# IGNITERS.net
KiCad netlist of a schematic drawn in Altium Designer
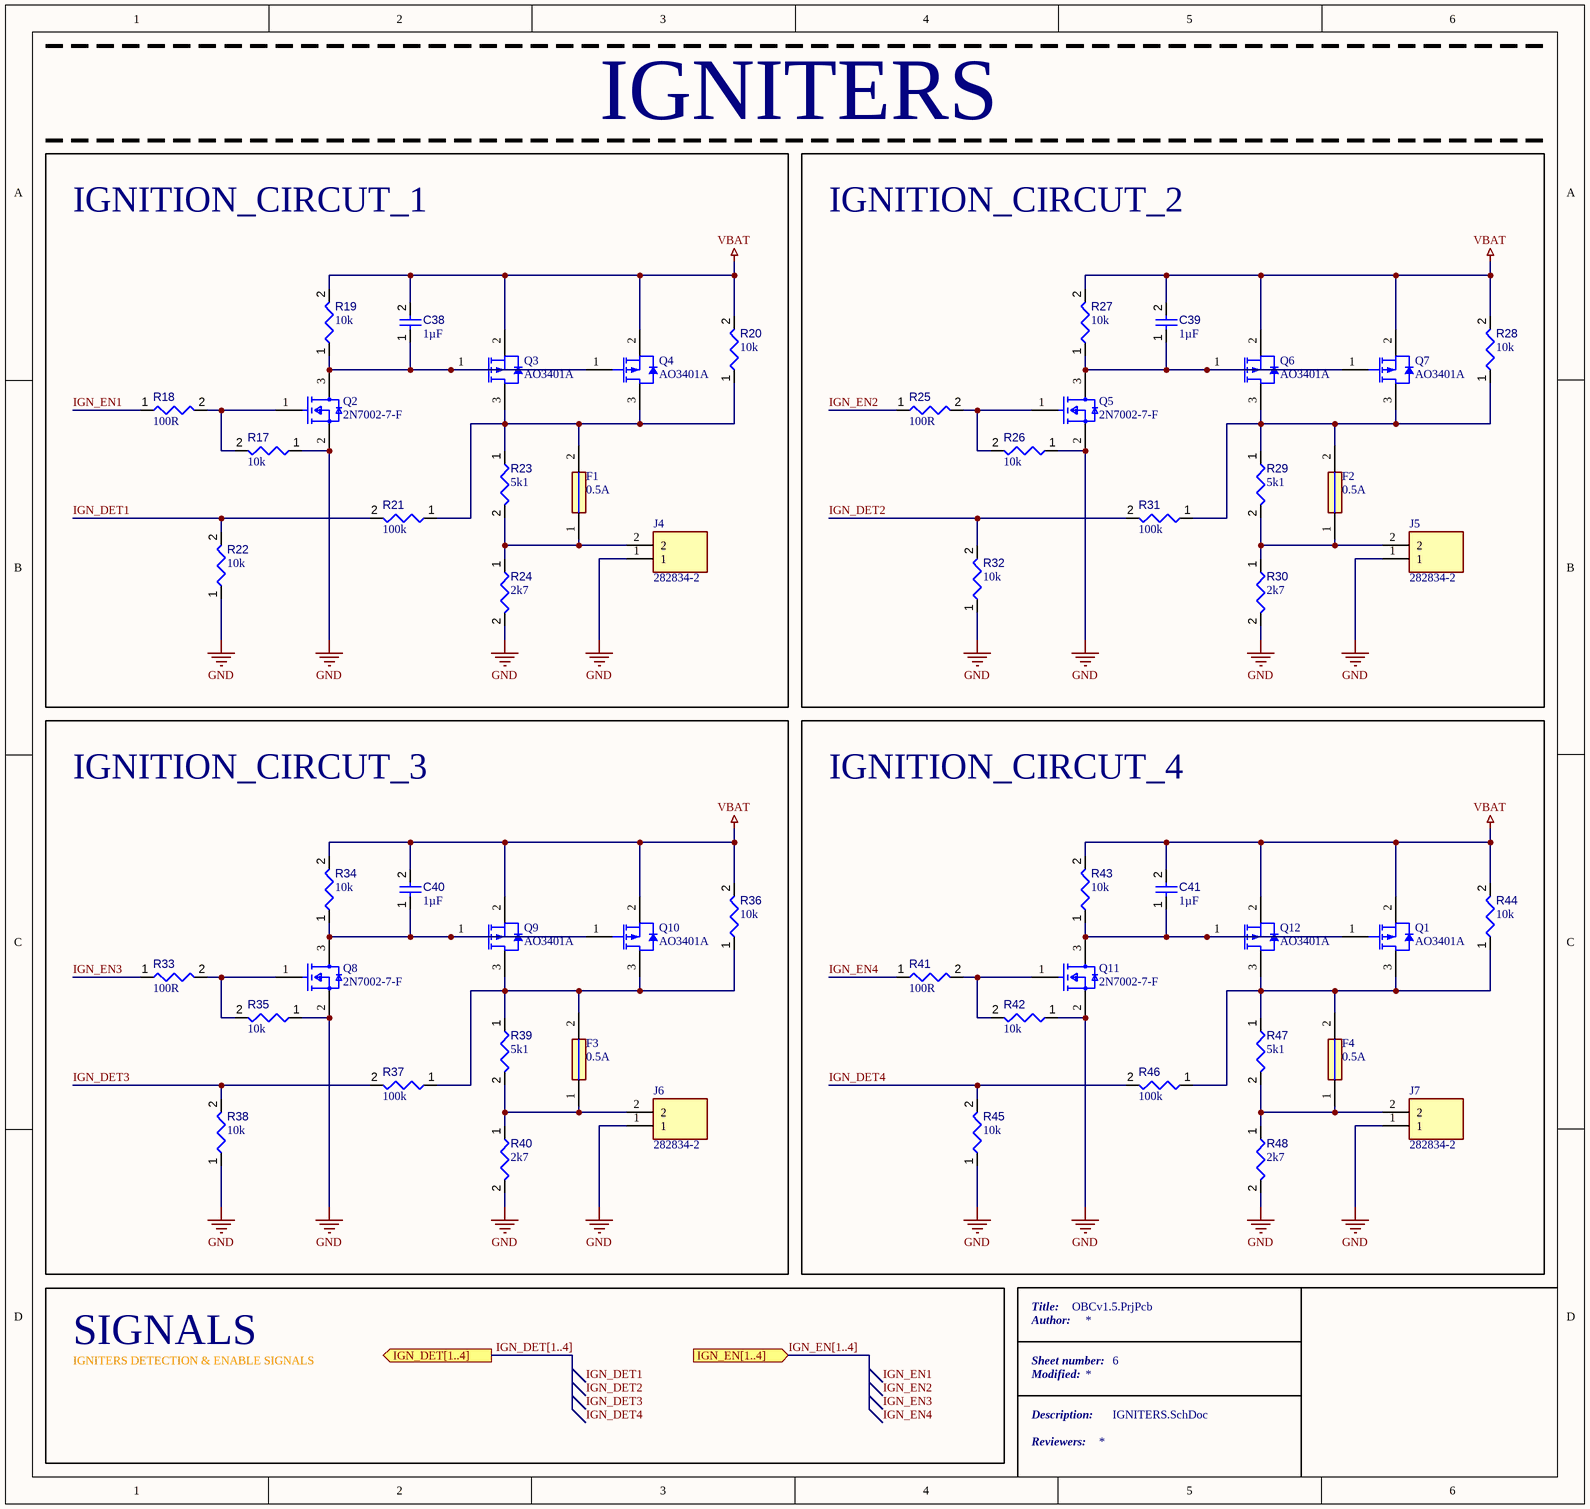
[diagram p0: IGNITERS.SchDoc]

(export (version "E")
  (design (tool "Eeschema 10.0.6"))
  (components
    (comp (ref "C38")
      (value "1µF")
      (footprint "CAPC0402(1005)60_L")
      (description "Chip Capacitor, 1µF +/-20%, 10V, 0402, Thickness 0.6 mm")
      (fields (field (name "TOLERANCE") "10%") (field (name "Comment") "Capacitor 1µF +/-20% 10V 0402"))
      (libsource (lib "PWr in Space team") (part "CAP-NP-2"))
    )
    (comp (ref "C39")
      (value "1µF")
      (footprint "CAPC0402(1005)60_L")
      (description "Chip Capacitor, 1µF +/-20%, 10V, 0402, Thickness 0.6 mm")
      (fields (field (name "TOLERANCE") "10%") (field (name "Comment") "Capacitor 1µF +/-20% 10V 0402"))
      (libsource (lib "PWr in Space team") (part "CAP-NP-2"))
    )
    (comp (ref "C40")
      (value "1µF")
      (footprint "CAPC0402(1005)60_L")
      (description "Chip Capacitor, 1µF +/-20%, 10V, 0402, Thickness 0.6 mm")
      (fields (field (name "TOLERANCE") "10%") (field (name "Comment") "Capacitor 1µF +/-20% 10V 0402"))
      (libsource (lib "PWr in Space team") (part "CAP-NP-2"))
    )
    (comp (ref "C41")
      (value "1µF")
      (footprint "CAPC0402(1005)60_L")
      (description "Chip Capacitor, 1µF +/-20%, 10V, 0402, Thickness 0.6 mm")
      (fields (field (name "TOLERANCE") "10%") (field (name "Comment") "Capacitor 1µF +/-20% 10V 0402"))
      (libsource (lib "PWr in Space team") (part "CAP-NP-2"))
    )
    (comp (ref "F1")
      (value "0.5A")
      (footprint "SamacSys:FUSC2516X100N")
      (description "Fuse")
      (fields (field (name "MANUFACTURER_PART_NUMBER") "PTSLR08058V300"))
      (libsource (lib "*") (part "PTSLR08058V300"))
    )
    (comp (ref "F2")
      (value "0.5A")
      (footprint "SamacSys:FUSC2516X100N")
      (description "Fuse")
      (fields (field (name "MANUFACTURER_PART_NUMBER") "PTSLR08058V300"))
      (libsource (lib "*") (part "PTSLR08058V300"))
    )
    (comp (ref "F3")
      (value "0.5A")
      (footprint "SamacSys:FUSC2516X100N")
      (description "Fuse")
      (fields (field (name "MANUFACTURER_PART_NUMBER") "PTSLR08058V300"))
      (libsource (lib "*") (part "PTSLR08058V300"))
    )
    (comp (ref "F4")
      (value "0.5A")
      (footprint "SamacSys:FUSC2516X100N")
      (description "Fuse")
      (fields (field (name "MANUFACTURER_PART_NUMBER") "PTSLR08058V300"))
      (libsource (lib "*") (part "PTSLR08058V300"))
    )
    (comp (ref "J4")
      (value "282834-2")
      (footprint "SamacSys:282834-2_1")
      (description "Connector")
      (fields (field (name "MOUSER PART NUMBER") "571-282834-2"))
      (libsource (lib "*") (part "282834-2"))
    )
    (comp (ref "J5")
      (value "282834-2")
      (footprint "SamacSys:282834-2_1")
      (description "Connector")
      (fields (field (name "MOUSER PART NUMBER") "571-282834-2"))
      (libsource (lib "*") (part "282834-2"))
    )
    (comp (ref "J6")
      (value "282834-2")
      (footprint "SamacSys:282834-2_1")
      (description "Connector")
      (fields (field (name "MOUSER PART NUMBER") "571-282834-2"))
      (libsource (lib "*") (part "282834-2"))
    )
    (comp (ref "J7")
      (value "282834-2")
      (footprint "SamacSys:282834-2_1")
      (description "Connector")
      (fields (field (name "MOUSER PART NUMBER") "571-282834-2"))
      (libsource (lib "*") (part "282834-2"))
    )
    (comp (ref "Q1")
      (value "AO3401A")
      (footprint "AO-SOT-23-3L_V")
      (description "P-Channel MOSFET, 30 V, 4 A, -55 to 150 degC, 3-Pin SOT-23-3L, RoHS, Tape and Reel")
      (fields (field (name "MANUFACTURER") "Alpha and Omega"))
      (libsource (lib "Altium Content Vault") (part "PEMOS-GSD-3"))
    )
    (comp (ref "Q2")
      (value "2N7002-7-F")
      (footprint "FP-SOT23-MFG")
      (description "MOSFET N-CH 60V 115MA SOT23-3")
      (fields (field (name "VOLTAGE") "60V"))
      (libsource (lib "Altium Content Vault") (part "3b9c635fedb024a5347a57b145af9cc"))
    )
    (comp (ref "Q3")
      (value "AO3401A")
      (footprint "AO-SOT-23-3L_V")
      (description "P-Channel MOSFET, 30 V, 4 A, -55 to 150 degC, 3-Pin SOT-23-3L, RoHS, Tape and Reel")
      (fields (field (name "MANUFACTURER") "Alpha and Omega"))
      (libsource (lib "Altium Content Vault") (part "PEMOS-GSD-3"))
    )
    (comp (ref "Q4")
      (value "AO3401A")
      (footprint "AO-SOT-23-3L_V")
      (description "P-Channel MOSFET, 30 V, 4 A, -55 to 150 degC, 3-Pin SOT-23-3L, RoHS, Tape and Reel")
      (fields (field (name "MANUFACTURER") "Alpha and Omega"))
      (libsource (lib "Altium Content Vault") (part "PEMOS-GSD-3"))
    )
    (comp (ref "Q5")
      (value "2N7002-7-F")
      (footprint "FP-SOT23-MFG")
      (description "MOSFET N-CH 60V 115MA SOT23-3")
      (fields (field (name "VOLTAGE") "60V"))
      (libsource (lib "Altium Content Vault") (part "3b9c635fedb024a5347a57b145af9cc"))
    )
    (comp (ref "Q6")
      (value "AO3401A")
      (footprint "AO-SOT-23-3L_V")
      (description "P-Channel MOSFET, 30 V, 4 A, -55 to 150 degC, 3-Pin SOT-23-3L, RoHS, Tape and Reel")
      (fields (field (name "MANUFACTURER") "Alpha and Omega"))
      (libsource (lib "Altium Content Vault") (part "PEMOS-GSD-3"))
    )
    (comp (ref "Q7")
      (value "AO3401A")
      (footprint "AO-SOT-23-3L_V")
      (description "P-Channel MOSFET, 30 V, 4 A, -55 to 150 degC, 3-Pin SOT-23-3L, RoHS, Tape and Reel")
      (fields (field (name "MANUFACTURER") "Alpha and Omega"))
      (libsource (lib "Altium Content Vault") (part "PEMOS-GSD-3"))
    )
    (comp (ref "Q8")
      (value "2N7002-7-F")
      (footprint "FP-SOT23-MFG")
      (description "MOSFET N-CH 60V 115MA SOT23-3")
      (fields (field (name "VOLTAGE") "60V"))
      (libsource (lib "Altium Content Vault") (part "3b9c635fedb024a5347a57b145af9cc"))
    )
    (comp (ref "Q9")
      (value "AO3401A")
      (footprint "AO-SOT-23-3L_V")
      (description "P-Channel MOSFET, 30 V, 4 A, -55 to 150 degC, 3-Pin SOT-23-3L, RoHS, Tape and Reel")
      (fields (field (name "MANUFACTURER") "Alpha and Omega"))
      (libsource (lib "Altium Content Vault") (part "PEMOS-GSD-3"))
    )
    (comp (ref "Q10")
      (value "AO3401A")
      (footprint "AO-SOT-23-3L_V")
      (description "P-Channel MOSFET, 30 V, 4 A, -55 to 150 degC, 3-Pin SOT-23-3L, RoHS, Tape and Reel")
      (fields (field (name "MANUFACTURER") "Alpha and Omega"))
      (libsource (lib "Altium Content Vault") (part "PEMOS-GSD-3"))
    )
    (comp (ref "Q11")
      (value "2N7002-7-F")
      (footprint "FP-SOT23-MFG")
      (description "MOSFET N-CH 60V 115MA SOT23-3")
      (fields (field (name "VOLTAGE") "60V"))
      (libsource (lib "Altium Content Vault") (part "3b9c635fedb024a5347a57b145af9cc"))
    )
    (comp (ref "Q12")
      (value "AO3401A")
      (footprint "AO-SOT-23-3L_V")
      (description "P-Channel MOSFET, 30 V, 4 A, -55 to 150 degC, 3-Pin SOT-23-3L, RoHS, Tape and Reel")
      (fields (field (name "MANUFACTURER") "Alpha and Omega"))
      (libsource (lib "Altium Content Vault") (part "PEMOS-GSD-3"))
    )
    (comp (ref "R17")
      (value "10k")
      (footprint "RESC0402(1005)_L")
      (description "Chip Resistor, 10 kOhms, +/-1 %, 63 mW, -55 to 125 degC, 0402")
      (fields (field (name "POWER") "63mW") (field (name "TOLERANCE") "1%"))
      (libsource (lib "PWr in Space team") (part "RES-2"))
    )
    (comp (ref "R18")
      (value "100R")
      (footprint "RESC0402(1005)_L")
      (description "Chip Resistor, 100 Ohms, +/-1 %, 63 mW, -55 to 155 degC, 0402")
      (fields (field (name "POWER") "63mW") (field (name "TOLERANCE") "1%"))
      (libsource (lib "PWr in Space team") (part "RES-2"))
    )
    (comp (ref "R19")
      (value "10k")
      (footprint "RESC0402(1005)_L")
      (description "Chip Resistor, 10 kOhms, +/-1 %, 63 mW, -55 to 125 degC, 0402")
      (fields (field (name "POWER") "63mW") (field (name "TOLERANCE") "1%"))
      (libsource (lib "PWr in Space team") (part "RES-2"))
    )
    (comp (ref "R20")
      (value "10k")
      (footprint "RESC0402(1005)_L")
      (description "Chip Resistor, 10 kOhms, +/-1 %, 63 mW, -55 to 125 degC, 0402")
      (fields (field (name "POWER") "63mW") (field (name "TOLERANCE") "1%"))
      (libsource (lib "PWr in Space team") (part "RES-2"))
    )
    (comp (ref "R21")
      (value "100k")
      (footprint "RESC0402(1005)_L")
      (description "Chip Resistor, 100 kOhms, +/-1 %, 63 mW, -55 to 155 degC, 0402")
      (fields (field (name "TOLERANCE") "1%") (field (name "POWER") "63mW"))
      (libsource (lib "PWr in Space team") (part "RES-2"))
    )
    (comp (ref "R22")
      (value "10k")
      (footprint "RESC0402(1005)_L")
      (description "Chip Resistor, 10 kOhms, +/-1 %, 63 mW, -55 to 125 degC, 0402")
      (fields (field (name "POWER") "63mW") (field (name "TOLERANCE") "1%"))
      (libsource (lib "PWr in Space team") (part "RES-2"))
    )
    (comp (ref "R23")
      (value "5k1")
      (footprint "RESC0402(1005)_L")
      (description "Chip Resistor, 5.1 kOhms, +/-1 %, 63 mW, -55 to 155 degC, 0402")
      (fields (field (name "TOLERANCE") "1%") (field (name "POWER") "63mW"))
      (libsource (lib "PWr in Space team") (part "RES-2"))
    )
    (comp (ref "R24")
      (value "2k7")
      (footprint "RESC0402(1005)_L")
      (description "Chip Resistor, 2.7 kOhms, +/-1 %, 63 mW, -55 to 155 degC, 0402")
      (fields (field (name "TOLERANCE") "1%") (field (name "POWER") "63mW"))
      (libsource (lib "PWr in Space team") (part "RES-2"))
    )
    (comp (ref "R25")
      (value "100R")
      (footprint "RESC0402(1005)_L")
      (description "Chip Resistor, 100 Ohms, +/-1 %, 63 mW, -55 to 155 degC, 0402")
      (fields (field (name "POWER") "63mW") (field (name "TOLERANCE") "1%"))
      (libsource (lib "PWr in Space team") (part "RES-2"))
    )
    (comp (ref "R26")
      (value "10k")
      (footprint "RESC0402(1005)_L")
      (description "Chip Resistor, 10 kOhms, +/-1 %, 63 mW, -55 to 125 degC, 0402")
      (fields (field (name "POWER") "63mW") (field (name "TOLERANCE") "1%"))
      (libsource (lib "PWr in Space team") (part "RES-2"))
    )
    (comp (ref "R27")
      (value "10k")
      (footprint "RESC0402(1005)_L")
      (description "Chip Resistor, 10 kOhms, +/-1 %, 63 mW, -55 to 125 degC, 0402")
      (fields (field (name "POWER") "63mW") (field (name "TOLERANCE") "1%"))
      (libsource (lib "PWr in Space team") (part "RES-2"))
    )
    (comp (ref "R28")
      (value "10k")
      (footprint "RESC0402(1005)_L")
      (description "Chip Resistor, 10 kOhms, +/-1 %, 63 mW, -55 to 125 degC, 0402")
      (fields (field (name "POWER") "63mW") (field (name "TOLERANCE") "1%"))
      (libsource (lib "PWr in Space team") (part "RES-2"))
    )
    (comp (ref "R29")
      (value "5k1")
      (footprint "RESC0402(1005)_L")
      (description "Chip Resistor, 5.1 kOhms, +/-1 %, 63 mW, -55 to 155 degC, 0402")
      (fields (field (name "TOLERANCE") "1%") (field (name "POWER") "63mW"))
      (libsource (lib "PWr in Space team") (part "RES-2"))
    )
    (comp (ref "R30")
      (value "2k7")
      (footprint "RESC0402(1005)_L")
      (description "Chip Resistor, 2.7 kOhms, +/-1 %, 63 mW, -55 to 155 degC, 0402")
      (fields (field (name "TOLERANCE") "1%") (field (name "POWER") "63mW"))
      (libsource (lib "PWr in Space team") (part "RES-2"))
    )
    (comp (ref "R31")
      (value "100k")
      (footprint "RESC0402(1005)_L")
      (description "Chip Resistor, 100 kOhms, +/-1 %, 63 mW, -55 to 155 degC, 0402")
      (fields (field (name "TOLERANCE") "1%") (field (name "POWER") "63mW"))
      (libsource (lib "PWr in Space team") (part "RES-2"))
    )
    (comp (ref "R32")
      (value "10k")
      (footprint "RESC0402(1005)_L")
      (description "Chip Resistor, 10 kOhms, +/-1 %, 63 mW, -55 to 125 degC, 0402")
      (fields (field (name "POWER") "63mW") (field (name "TOLERANCE") "1%"))
      (libsource (lib "PWr in Space team") (part "RES-2"))
    )
    (comp (ref "R33")
      (value "100R")
      (footprint "RESC0402(1005)_L")
      (description "Chip Resistor, 100 Ohms, +/-1 %, 63 mW, -55 to 155 degC, 0402")
      (fields (field (name "POWER") "63mW") (field (name "TOLERANCE") "1%"))
      (libsource (lib "PWr in Space team") (part "RES-2"))
    )
    (comp (ref "R34")
      (value "10k")
      (footprint "RESC0402(1005)_L")
      (description "Chip Resistor, 10 kOhms, +/-1 %, 63 mW, -55 to 125 degC, 0402")
      (fields (field (name "POWER") "63mW") (field (name "TOLERANCE") "1%"))
      (libsource (lib "PWr in Space team") (part "RES-2"))
    )
    (comp (ref "R35")
      (value "10k")
      (footprint "RESC0402(1005)_L")
      (description "Chip Resistor, 10 kOhms, +/-1 %, 63 mW, -55 to 125 degC, 0402")
      (fields (field (name "POWER") "63mW") (field (name "TOLERANCE") "1%"))
      (libsource (lib "PWr in Space team") (part "RES-2"))
    )
    (comp (ref "R36")
      (value "10k")
      (footprint "RESC0402(1005)_L")
      (description "Chip Resistor, 10 kOhms, +/-1 %, 63 mW, -55 to 125 degC, 0402")
      (fields (field (name "POWER") "63mW") (field (name "TOLERANCE") "1%"))
      (libsource (lib "PWr in Space team") (part "RES-2"))
    )
    (comp (ref "R37")
      (value "100k")
      (footprint "RESC0402(1005)_L")
      (description "Chip Resistor, 100 kOhms, +/-1 %, 63 mW, -55 to 155 degC, 0402")
      (fields (field (name "TOLERANCE") "1%") (field (name "POWER") "63mW"))
      (libsource (lib "PWr in Space team") (part "RES-2"))
    )
    (comp (ref "R38")
      (value "10k")
      (footprint "RESC0402(1005)_L")
      (description "Chip Resistor, 10 kOhms, +/-1 %, 63 mW, -55 to 125 degC, 0402")
      (fields (field (name "POWER") "63mW") (field (name "TOLERANCE") "1%"))
      (libsource (lib "PWr in Space team") (part "RES-2"))
    )
    (comp (ref "R39")
      (value "5k1")
      (footprint "RESC0402(1005)_L")
      (description "Chip Resistor, 5.1 kOhms, +/-1 %, 63 mW, -55 to 155 degC, 0402")
      (fields (field (name "TOLERANCE") "1%") (field (name "POWER") "63mW"))
      (libsource (lib "PWr in Space team") (part "RES-2"))
    )
    (comp (ref "R40")
      (value "2k7")
      (footprint "RESC0402(1005)_L")
      (description "Chip Resistor, 2.7 kOhms, +/-1 %, 63 mW, -55 to 155 degC, 0402")
      (fields (field (name "TOLERANCE") "1%") (field (name "POWER") "63mW"))
      (libsource (lib "PWr in Space team") (part "RES-2"))
    )
    (comp (ref "R41")
      (value "100R")
      (footprint "RESC0402(1005)_L")
      (description "Chip Resistor, 100 Ohms, +/-1 %, 63 mW, -55 to 155 degC, 0402")
      (fields (field (name "POWER") "63mW") (field (name "TOLERANCE") "1%"))
      (libsource (lib "PWr in Space team") (part "RES-2"))
    )
    (comp (ref "R42")
      (value "10k")
      (footprint "RESC0402(1005)_L")
      (description "Chip Resistor, 10 kOhms, +/-1 %, 63 mW, -55 to 125 degC, 0402")
      (fields (field (name "POWER") "63mW") (field (name "TOLERANCE") "1%"))
      (libsource (lib "PWr in Space team") (part "RES-2"))
    )
    (comp (ref "R43")
      (value "10k")
      (footprint "RESC0402(1005)_L")
      (description "Chip Resistor, 10 kOhms, +/-1 %, 63 mW, -55 to 125 degC, 0402")
      (fields (field (name "POWER") "63mW") (field (name "TOLERANCE") "1%"))
      (libsource (lib "PWr in Space team") (part "RES-2"))
    )
    (comp (ref "R44")
      (value "10k")
      (footprint "RESC0402(1005)_L")
      (description "Chip Resistor, 10 kOhms, +/-1 %, 63 mW, -55 to 125 degC, 0402")
      (fields (field (name "POWER") "63mW") (field (name "TOLERANCE") "1%"))
      (libsource (lib "PWr in Space team") (part "RES-2"))
    )
    (comp (ref "R45")
      (value "10k")
      (footprint "RESC0402(1005)_L")
      (description "Chip Resistor, 10 kOhms, +/-1 %, 63 mW, -55 to 125 degC, 0402")
      (fields (field (name "POWER") "63mW") (field (name "TOLERANCE") "1%"))
      (libsource (lib "PWr in Space team") (part "RES-2"))
    )
    (comp (ref "R46")
      (value "100k")
      (footprint "RESC0402(1005)_L")
      (description "Chip Resistor, 100 kOhms, +/-1 %, 63 mW, -55 to 155 degC, 0402")
      (fields (field (name "TOLERANCE") "1%") (field (name "POWER") "63mW"))
      (libsource (lib "PWr in Space team") (part "RES-2"))
    )
    (comp (ref "R47")
      (value "5k1")
      (footprint "RESC0402(1005)_L")
      (description "Chip Resistor, 5.1 kOhms, +/-1 %, 63 mW, -55 to 155 degC, 0402")
      (fields (field (name "TOLERANCE") "1%") (field (name "POWER") "63mW"))
      (libsource (lib "PWr in Space team") (part "RES-2"))
    )
    (comp (ref "R48")
      (value "2k7")
      (footprint "RESC0402(1005)_L")
      (description "Chip Resistor, 2.7 kOhms, +/-1 %, 63 mW, -55 to 155 degC, 0402")
      (fields (field (name "TOLERANCE") "1%") (field (name "POWER") "63mW"))
      (libsource (lib "PWr in Space team") (part "RES-2"))
    )
  )
  (nets
    (net (code "1") (name "/IGN_DET1") (class "Default")
      (node (ref "R21") (pin "2") (pinfunction "2_2") (pintype "passive"))
      (node (ref "R22") (pin "2") (pinfunction "2_2") (pintype "passive"))
    )
    (net (code "2") (name "/IGN_DET2") (class "Default")
      (node (ref "R31") (pin "2") (pinfunction "2_2") (pintype "passive"))
      (node (ref "R32") (pin "2") (pinfunction "2_2") (pintype "passive"))
    )
    (net (code "3") (name "/IGN_DET3") (class "Default")
      (node (ref "R37") (pin "2") (pinfunction "2_2") (pintype "passive"))
      (node (ref "R38") (pin "2") (pinfunction "2_2") (pintype "passive"))
    )
    (net (code "4") (name "/IGN_DET4") (class "Default")
      (node (ref "R45") (pin "2") (pinfunction "2_2") (pintype "passive"))
      (node (ref "R46") (pin "2") (pinfunction "2_2") (pintype "passive"))
    )
    (net (code "6") (name "/IGN_EN1") (class "Default")
      (node (ref "R18") (pin "1") (pinfunction "1_1") (pintype "passive"))
    )
    (net (code "7") (name "/IGN_EN2") (class "Default")
      (node (ref "R25") (pin "1") (pinfunction "1_1") (pintype "passive"))
    )
    (net (code "8") (name "/IGN_EN3") (class "Default")
      (node (ref "R33") (pin "1") (pinfunction "1_1") (pintype "passive"))
    )
    (net (code "9") (name "/IGN_EN4") (class "Default")
      (node (ref "R41") (pin "1") (pinfunction "1_1") (pintype "passive"))
    )
    (net (code "11") (name "GND") (class "Default")
      (node (ref "J4") (pin "1") (pinfunction "1_1") (pintype "passive"))
      (node (ref "J5") (pin "1") (pinfunction "1_1") (pintype "passive"))
      (node (ref "J6") (pin "1") (pinfunction "1_1") (pintype "passive"))
      (node (ref "J7") (pin "1") (pinfunction "1_1") (pintype "passive"))
      (node (ref "Q11") (pin "2") (pinfunction "S_2") (pintype "passive"))
      (node (ref "Q2") (pin "2") (pinfunction "S_2") (pintype "passive"))
      (node (ref "Q5") (pin "2") (pinfunction "S_2") (pintype "passive"))
      (node (ref "Q8") (pin "2") (pinfunction "S_2") (pintype "passive"))
      (node (ref "R17") (pin "1") (pinfunction "1_1") (pintype "passive"))
      (node (ref "R22") (pin "1") (pinfunction "1_1") (pintype "passive"))
      (node (ref "R24") (pin "2") (pinfunction "2_2") (pintype "passive"))
      (node (ref "R26") (pin "1") (pinfunction "1_1") (pintype "passive"))
      (node (ref "R30") (pin "2") (pinfunction "2_2") (pintype "passive"))
      (node (ref "R32") (pin "1") (pinfunction "1_1") (pintype "passive"))
      (node (ref "R35") (pin "1") (pinfunction "1_1") (pintype "passive"))
      (node (ref "R38") (pin "1") (pinfunction "1_1") (pintype "passive"))
      (node (ref "R40") (pin "2") (pinfunction "2_2") (pintype "passive"))
      (node (ref "R42") (pin "1") (pinfunction "1_1") (pintype "passive"))
      (node (ref "R45") (pin "1") (pinfunction "1_1") (pintype "passive"))
      (node (ref "R48") (pin "2") (pinfunction "2_2") (pintype "passive"))
    )
    (net (code "12") (name "Net-(F1-Pad1)") (class "Default")
      (node (ref "F1") (pin "1") (pinfunction "1_1") (pintype "passive"))
      (node (ref "J4") (pin "2") (pinfunction "2_2") (pintype "passive"))
      (node (ref "R23") (pin "2") (pinfunction "2_2") (pintype "passive"))
      (node (ref "R24") (pin "1") (pinfunction "1_1") (pintype "passive"))
    )
    (net (code "13") (name "Net-(F2-Pad1)") (class "Default")
      (node (ref "F2") (pin "1") (pinfunction "1_1") (pintype "passive"))
      (node (ref "J5") (pin "2") (pinfunction "2_2") (pintype "passive"))
      (node (ref "R29") (pin "2") (pinfunction "2_2") (pintype "passive"))
      (node (ref "R30") (pin "1") (pinfunction "1_1") (pintype "passive"))
    )
    (net (code "14") (name "Net-(F3-Pad1)") (class "Default")
      (node (ref "F3") (pin "1") (pinfunction "1_1") (pintype "passive"))
      (node (ref "J6") (pin "2") (pinfunction "2_2") (pintype "passive"))
      (node (ref "R39") (pin "2") (pinfunction "2_2") (pintype "passive"))
      (node (ref "R40") (pin "1") (pinfunction "1_1") (pintype "passive"))
    )
    (net (code "15") (name "Net-(F4-Pad1)") (class "Default")
      (node (ref "F4") (pin "1") (pinfunction "1_1") (pintype "passive"))
      (node (ref "J7") (pin "2") (pinfunction "2_2") (pintype "passive"))
      (node (ref "R47") (pin "2") (pinfunction "2_2") (pintype "passive"))
      (node (ref "R48") (pin "1") (pinfunction "1_1") (pintype "passive"))
    )
    (net (code "16") (name "Net-(Q1-DRAIN)") (class "Default")
      (node (ref "F4") (pin "2") (pinfunction "2_2") (pintype "passive"))
      (node (ref "Q1") (pin "3") (pinfunction "DRAIN_3") (pintype "passive"))
      (node (ref "Q12") (pin "3") (pinfunction "DRAIN_3") (pintype "passive"))
      (node (ref "R44") (pin "1") (pinfunction "1_1") (pintype "passive"))
      (node (ref "R46") (pin "1") (pinfunction "1_1") (pintype "passive"))
      (node (ref "R47") (pin "1") (pinfunction "1_1") (pintype "passive"))
    )
    (net (code "17") (name "Net-(Q1-GATE)") (class "Default")
      (node (ref "C41") (pin "1") (pinfunction "1_1") (pintype "passive"))
      (node (ref "Q1") (pin "1") (pinfunction "GATE_1") (pintype "passive"))
      (node (ref "Q11") (pin "3") (pinfunction "D_3") (pintype "passive"))
      (node (ref "Q12") (pin "1") (pinfunction "GATE_1") (pintype "passive"))
      (node (ref "R43") (pin "1") (pinfunction "1_1") (pintype "passive"))
    )
    (net (code "18") (name "Net-(Q2-D)") (class "Default")
      (node (ref "C38") (pin "1") (pinfunction "1_1") (pintype "passive"))
      (node (ref "Q2") (pin "3") (pinfunction "D_3") (pintype "passive"))
      (node (ref "Q3") (pin "1") (pinfunction "GATE_1") (pintype "passive"))
      (node (ref "Q4") (pin "1") (pinfunction "GATE_1") (pintype "passive"))
      (node (ref "R19") (pin "1") (pinfunction "1_1") (pintype "passive"))
    )
    (net (code "19") (name "Net-(Q2-G)") (class "Default")
      (node (ref "Q2") (pin "1") (pinfunction "G_1") (pintype "passive"))
      (node (ref "R17") (pin "2") (pinfunction "2_2") (pintype "passive"))
      (node (ref "R18") (pin "2") (pinfunction "2_2") (pintype "passive"))
    )
    (net (code "20") (name "Net-(Q3-DRAIN)") (class "Default")
      (node (ref "F1") (pin "2") (pinfunction "2_2") (pintype "passive"))
      (node (ref "Q3") (pin "3") (pinfunction "DRAIN_3") (pintype "passive"))
      (node (ref "Q4") (pin "3") (pinfunction "DRAIN_3") (pintype "passive"))
      (node (ref "R20") (pin "1") (pinfunction "1_1") (pintype "passive"))
      (node (ref "R21") (pin "1") (pinfunction "1_1") (pintype "passive"))
      (node (ref "R23") (pin "1") (pinfunction "1_1") (pintype "passive"))
    )
    (net (code "21") (name "Net-(Q5-D)") (class "Default")
      (node (ref "C39") (pin "1") (pinfunction "1_1") (pintype "passive"))
      (node (ref "Q5") (pin "3") (pinfunction "D_3") (pintype "passive"))
      (node (ref "Q6") (pin "1") (pinfunction "GATE_1") (pintype "passive"))
      (node (ref "Q7") (pin "1") (pinfunction "GATE_1") (pintype "passive"))
      (node (ref "R27") (pin "1") (pinfunction "1_1") (pintype "passive"))
    )
    (net (code "22") (name "Net-(Q5-G)") (class "Default")
      (node (ref "Q5") (pin "1") (pinfunction "G_1") (pintype "passive"))
      (node (ref "R25") (pin "2") (pinfunction "2_2") (pintype "passive"))
      (node (ref "R26") (pin "2") (pinfunction "2_2") (pintype "passive"))
    )
    (net (code "23") (name "Net-(Q6-DRAIN)") (class "Default")
      (node (ref "F2") (pin "2") (pinfunction "2_2") (pintype "passive"))
      (node (ref "Q6") (pin "3") (pinfunction "DRAIN_3") (pintype "passive"))
      (node (ref "Q7") (pin "3") (pinfunction "DRAIN_3") (pintype "passive"))
      (node (ref "R28") (pin "1") (pinfunction "1_1") (pintype "passive"))
      (node (ref "R29") (pin "1") (pinfunction "1_1") (pintype "passive"))
      (node (ref "R31") (pin "1") (pinfunction "1_1") (pintype "passive"))
    )
    (net (code "24") (name "Net-(Q8-G)") (class "Default")
      (node (ref "Q8") (pin "1") (pinfunction "G_1") (pintype "passive"))
      (node (ref "R33") (pin "2") (pinfunction "2_2") (pintype "passive"))
      (node (ref "R35") (pin "2") (pinfunction "2_2") (pintype "passive"))
    )
    (net (code "25") (name "Net-(Q10-DRAIN)") (class "Default")
      (node (ref "F3") (pin "2") (pinfunction "2_2") (pintype "passive"))
      (node (ref "Q10") (pin "3") (pinfunction "DRAIN_3") (pintype "passive"))
      (node (ref "Q9") (pin "3") (pinfunction "DRAIN_3") (pintype "passive"))
      (node (ref "R36") (pin "1") (pinfunction "1_1") (pintype "passive"))
      (node (ref "R37") (pin "1") (pinfunction "1_1") (pintype "passive"))
      (node (ref "R39") (pin "1") (pinfunction "1_1") (pintype "passive"))
    )
    (net (code "26") (name "Net-(Q10-GATE)") (class "Default")
      (node (ref "C40") (pin "1") (pinfunction "1_1") (pintype "passive"))
      (node (ref "Q10") (pin "1") (pinfunction "GATE_1") (pintype "passive"))
      (node (ref "Q8") (pin "3") (pinfunction "D_3") (pintype "passive"))
      (node (ref "Q9") (pin "1") (pinfunction "GATE_1") (pintype "passive"))
      (node (ref "R34") (pin "1") (pinfunction "1_1") (pintype "passive"))
    )
    (net (code "27") (name "Net-(Q11-G)") (class "Default")
      (node (ref "Q11") (pin "1") (pinfunction "G_1") (pintype "passive"))
      (node (ref "R41") (pin "2") (pinfunction "2_2") (pintype "passive"))
      (node (ref "R42") (pin "2") (pinfunction "2_2") (pintype "passive"))
    )
    (net (code "28") (name "VBAT") (class "Default")
      (node (ref "C38") (pin "2") (pinfunction "2_2") (pintype "passive"))
      (node (ref "C39") (pin "2") (pinfunction "2_2") (pintype "passive"))
      (node (ref "C40") (pin "2") (pinfunction "2_2") (pintype "passive"))
      (node (ref "C41") (pin "2") (pinfunction "2_2") (pintype "passive"))
      (node (ref "Q1") (pin "2") (pinfunction "SOURCE_2") (pintype "passive"))
      (node (ref "Q10") (pin "2") (pinfunction "SOURCE_2") (pintype "passive"))
      (node (ref "Q12") (pin "2") (pinfunction "SOURCE_2") (pintype "passive"))
      (node (ref "Q3") (pin "2") (pinfunction "SOURCE_2") (pintype "passive"))
      (node (ref "Q4") (pin "2") (pinfunction "SOURCE_2") (pintype "passive"))
      (node (ref "Q6") (pin "2") (pinfunction "SOURCE_2") (pintype "passive"))
      (node (ref "Q7") (pin "2") (pinfunction "SOURCE_2") (pintype "passive"))
      (node (ref "Q9") (pin "2") (pinfunction "SOURCE_2") (pintype "passive"))
      (node (ref "R19") (pin "2") (pinfunction "2_2") (pintype "passive"))
      (node (ref "R20") (pin "2") (pinfunction "2_2") (pintype "passive"))
      (node (ref "R27") (pin "2") (pinfunction "2_2") (pintype "passive"))
      (node (ref "R28") (pin "2") (pinfunction "2_2") (pintype "passive"))
      (node (ref "R34") (pin "2") (pinfunction "2_2") (pintype "passive"))
      (node (ref "R36") (pin "2") (pinfunction "2_2") (pintype "passive"))
      (node (ref "R43") (pin "2") (pinfunction "2_2") (pintype "passive"))
      (node (ref "R44") (pin "2") (pinfunction "2_2") (pintype "passive"))
    )
  )
)
